# sensor.net
KiCad netlist of a schematic drawn in Altium Designer
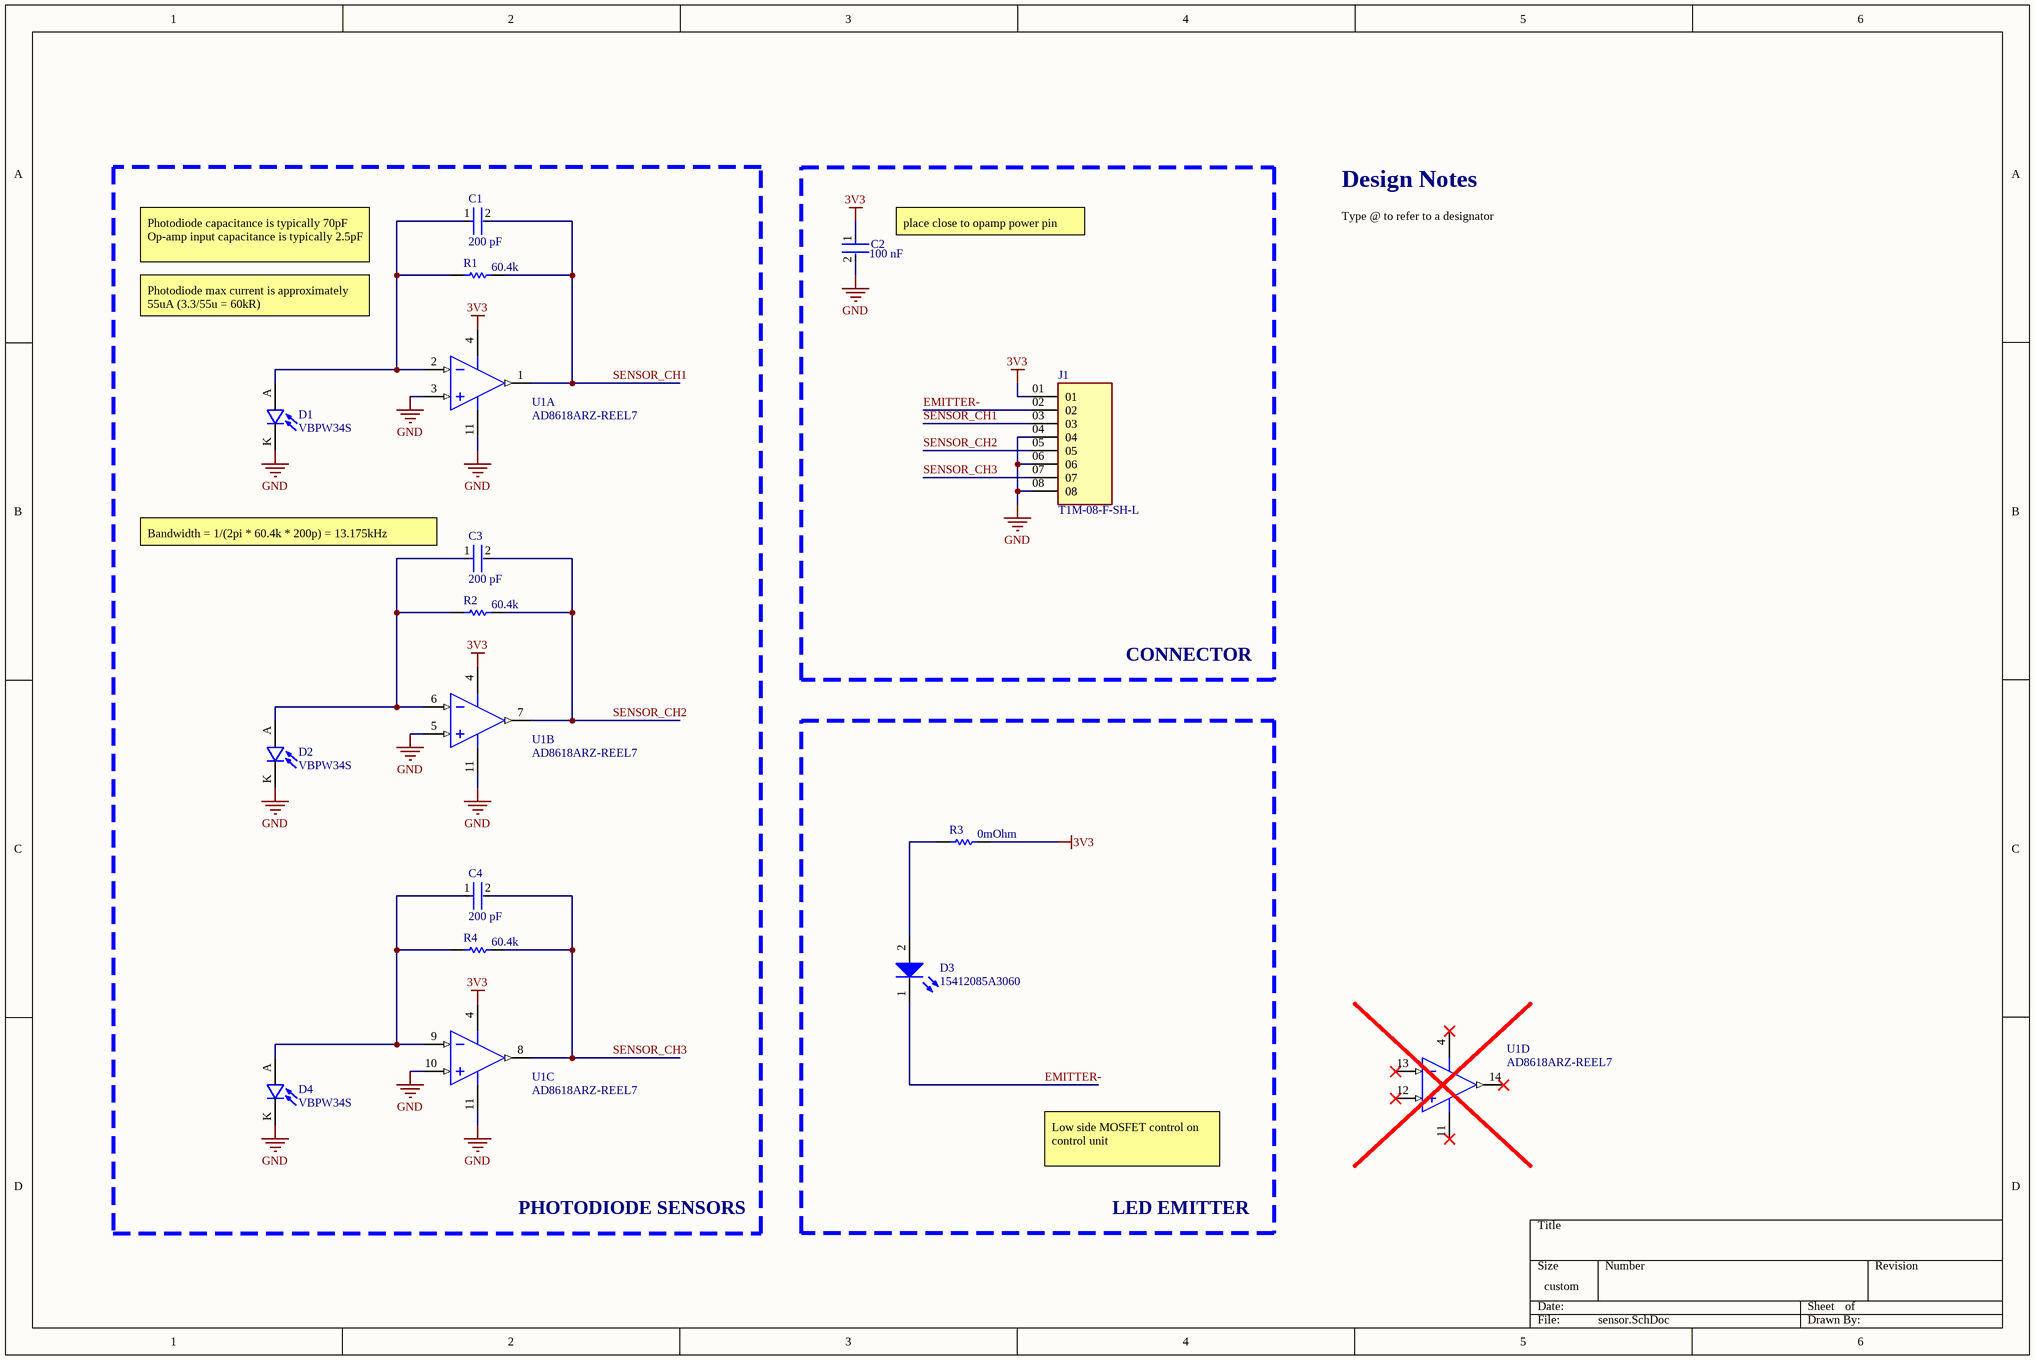
[diagram p0: sensor.SchDoc]

(export (version "E")
  (design (tool "Eeschema 10.0.6"))
  (components
    (comp (ref "C1")
      (value "C0603C201J5GACTU")
      (footprint "FP-C0603C-CF-MFG")
      (description "CAP CER 200PF 50V 5% NP0 0603")
      (fields
        (field (name "CAPACITANCE") "200 pF")
        (field (name "MANUFACTURER") "KEMET")
        (field (name "OCTOPART") "https://octopart.com/c0603c201j5gactu-kemet-9143917")
      )
      (libsource (lib "Altium Content Vault") (part "b4654b650e69147ec39a6b967a45e02"))
    )
    (comp (ref "C2")
      (value "CC0603KRX7R7BB104")
      (footprint "FP-CC0603-DA-MFG")
      (description "CAP CER 0.1UF 16V X7R 0603")
      (fields
        (field (name "OCTOPART") "https://octopart.com/cc0603krx7r7bb104-yageo-192941")
        (field (name "TOLERANCE") "0.1")
        (field (name "CAPACITANCE") "100 nF")
      )
      (libsource (lib "Altium Content Vault") (part "11868f565c42a9108669ba33697ecf6"))
    )
    (comp (ref "C3")
      (value "C0603C201J5GACTU")
      (footprint "FP-C0603C-CF-MFG")
      (description "CAP CER 200PF 50V 5% NP0 0603")
      (fields
        (field (name "CAPACITANCE") "200 pF")
        (field (name "MANUFACTURER") "KEMET")
        (field (name "OCTOPART") "https://octopart.com/c0603c201j5gactu-kemet-9143917")
      )
      (libsource (lib "Altium Content Vault") (part "b4654b650e69147ec39a6b967a45e02"))
    )
    (comp (ref "C4")
      (value "C0603C201J5GACTU")
      (footprint "FP-C0603C-CF-MFG")
      (description "CAP CER 200PF 50V 5% NP0 0603")
      (fields
        (field (name "CAPACITANCE") "200 pF")
        (field (name "MANUFACTURER") "KEMET")
        (field (name "OCTOPART") "https://octopart.com/c0603c201j5gactu-kemet-9143917")
      )
      (libsource (lib "Altium Content Vault") (part "b4654b650e69147ec39a6b967a45e02"))
    )
    (comp (ref "D1")
      (value "VBPW34S")
      (footprint "PcbLib1:XDCR_VBPW34S")
      (description "Photodiode 940nm 100ns 130Â° 2-SMD, Gull Wing")
      (fields (field (name "MF") "Vishay"))
      (libsource (lib "Schlib1") (part "VBPW34S"))
    )
    (comp (ref "D2")
      (value "VBPW34S")
      (footprint "PcbLib1:XDCR_VBPW34S")
      (description "Photodiode 940nm 100ns 130Â° 2-SMD, Gull Wing")
      (fields (field (name "MF") "Vishay"))
      (libsource (lib "Schlib1") (part "VBPW34S"))
    )
    (comp (ref "D3")
      (value "15412085A3060")
      (footprint "WL-SIRW_1206")
      (description "15412085A3060 WL-SIRW SMT Infrared Reverse mount Waterclear Dome")
      (libsource (lib "Altium Content Vault") (part "LED_Infrared_2A-1K"))
    )
    (comp (ref "D4")
      (value "VBPW34S")
      (footprint "PcbLib1:XDCR_VBPW34S")
      (description "Photodiode 940nm 100ns 130Â° 2-SMD, Gull Wing")
      (fields (field (name "MF") "Vishay"))
      (libsource (lib "Schlib1") (part "VBPW34S"))
    )
    (comp (ref "J1")
      (value "T1M-08-F-SH-L")
      (footprint "PcbLib1:SAMTEC_T1M-08-F-SH-L")
      (fields (field (name "MF") "Samtec Inc."))
      (libsource (lib "Schlib1") (part "T1M-08-F-SH-L"))
    )
    (comp (ref "R1")
      (value "RC0603FR-0760K4L")
      (footprint "RESC1608X55X25ML10T15")
      (fields (field (name "MANUFACTURER") "Yageo") (field (name "RESISTANCE") "60.4k"))
      (libsource (lib "Altium Content Vault") (part "RES"))
    )
    (comp (ref "R2")
      (value "RC0603FR-0760K4L")
      (footprint "RESC1608X55X25ML10T15")
      (fields (field (name "MANUFACTURER") "Yageo") (field (name "RESISTANCE") "60.4k"))
      (libsource (lib "Altium Content Vault") (part "RES"))
    )
    (comp (ref "R3")
      (value "RC0603JR-070RL")
      (footprint "RESC1608X55X25ML10T15")
      (description "Chip Resistor, 0 Ohm, +/- 5%, 0.1 W, -55 to 155 degC, 0603 (1608 Metric), RoHS, Tape and Reel")
      (fields
        (field (name "TOLERANCE") "5%")
        (field (name "RESISTANCE") "0mOhm")
        (field (name "MANUFACTURER") "Yageo")
      )
      (libsource (lib "Altium Content Vault") (part "RES-2"))
    )
    (comp (ref "R4")
      (value "RC0603FR-0760K4L")
      (footprint "RESC1608X55X25ML10T15")
      (fields (field (name "MANUFACTURER") "Yageo") (field (name "RESISTANCE") "60.4k"))
      (libsource (lib "Altium Content Vault") (part "RES"))
    )
    (comp (ref "U1")
      (value "AD8618ARZ-REEL7")
      (footprint "ADI-R-14_M")
      (fields (field (name "GENERIC PART NUMBER") "AD8618") (field (name "MANUFACTURER") "Analog Devices"))
      (libsource (lib "Altium Content Vault") (part "ADI-ADxxxx_OPxxxx-X-14"))
    )
  )
  (nets
    (net (code "1") (name "/EMITTER-") (class "Default")
      (node (ref "D3") (pin "1") (pinfunction "K_1") (pintype "passive"))
      (node (ref "J1") (pin "02") (pinfunction "02_02") (pintype "passive"))
    )
    (net (code "2") (name "/SENSOR_CH1") (class "Default")
      (node (ref "C1") (pin "2") (pinfunction "2_2") (pintype "passive"))
      (node (ref "J1") (pin "03") (pinfunction "03_03") (pintype "passive"))
      (node (ref "R1") (pin "2") (pinfunction "2_2") (pintype "passive"))
      (node (ref "U1") (pin "1") (pinfunction "OUT_A_1") (pintype "output"))
    )
    (net (code "3") (name "/SENSOR_CH2") (class "Default")
      (node (ref "C3") (pin "2") (pinfunction "2_2") (pintype "passive"))
      (node (ref "J1") (pin "05") (pinfunction "05_05") (pintype "passive"))
      (node (ref "R2") (pin "2") (pinfunction "2_2") (pintype "passive"))
      (node (ref "U1") (pin "7") (pinfunction "OUT_B_7") (pintype "output"))
    )
    (net (code "4") (name "/SENSOR_CH3") (class "Default")
      (node (ref "C4") (pin "2") (pinfunction "2_2") (pintype "passive"))
      (node (ref "J1") (pin "07") (pinfunction "07_07") (pintype "passive"))
      (node (ref "R4") (pin "2") (pinfunction "2_2") (pintype "passive"))
      (node (ref "U1") (pin "8") (pinfunction "OUT_C_8") (pintype "output"))
    )
    (net (code "5") (name "3V3") (class "Default")
      (node (ref "C2") (pin "1") (pinfunction "1_1") (pintype "passive"))
      (node (ref "J1") (pin "01") (pinfunction "01_01") (pintype "passive"))
      (node (ref "R3") (pin "2") (pinfunction "2_2") (pintype "passive"))
      (node (ref "U1") (pin "4") (pinfunction "+V_4") (pintype "power_in"))
    )
    (net (code "6") (name "GND") (class "Default")
      (node (ref "C2") (pin "2") (pinfunction "2_2") (pintype "passive"))
      (node (ref "D1") (pin "K") (pinfunction "C_K") (pintype "passive"))
      (node (ref "D2") (pin "K") (pinfunction "C_K") (pintype "passive"))
      (node (ref "D4") (pin "K") (pinfunction "C_K") (pintype "passive"))
      (node (ref "J1") (pin "04") (pinfunction "04_04") (pintype "passive"))
      (node (ref "J1") (pin "06") (pinfunction "06_06") (pintype "passive"))
      (node (ref "J1") (pin "08") (pinfunction "08_08") (pintype "passive"))
      (node (ref "U1") (pin "10") (pinfunction "+IN_C_10") (pintype "input"))
      (node (ref "U1") (pin "11") (pinfunction "-V_11") (pintype "power_in"))
      (node (ref "U1") (pin "3") (pinfunction "+IN_A_3") (pintype "input"))
      (node (ref "U1") (pin "5") (pinfunction "+IN_B_5") (pintype "input"))
    )
    (net (code "7") (name "Net-(D3-A)") (class "Default")
      (node (ref "D3") (pin "2") (pinfunction "A_2") (pintype "passive"))
      (node (ref "R3") (pin "1") (pinfunction "1_1") (pintype "passive"))
    )
    (net (code "8") (name "Net-(U1A--IN_A)") (class "Default")
      (node (ref "C1") (pin "1") (pinfunction "1_1") (pintype "passive"))
      (node (ref "D1") (pin "A") (pinfunction "A_A") (pintype "passive"))
      (node (ref "R1") (pin "1") (pinfunction "1_1") (pintype "passive"))
      (node (ref "U1") (pin "2") (pinfunction "-IN_A_2") (pintype "input"))
    )
    (net (code "9") (name "Net-(U1B--IN_B)") (class "Default")
      (node (ref "C3") (pin "1") (pinfunction "1_1") (pintype "passive"))
      (node (ref "D2") (pin "A") (pinfunction "A_A") (pintype "passive"))
      (node (ref "R2") (pin "1") (pinfunction "1_1") (pintype "passive"))
      (node (ref "U1") (pin "6") (pinfunction "-IN_B_6") (pintype "input"))
    )
    (net (code "10") (name "Net-(U1C--IN_C)") (class "Default")
      (node (ref "C4") (pin "1") (pinfunction "1_1") (pintype "passive"))
      (node (ref "D4") (pin "A") (pinfunction "A_A") (pintype "passive"))
      (node (ref "R4") (pin "1") (pinfunction "1_1") (pintype "passive"))
      (node (ref "U1") (pin "9") (pinfunction "-IN_C_9") (pintype "input"))
    )
    (net (code "11") (name "unconnected-(U1D-+IN_D-Pad12)") (class "Default")
      (node (ref "U1") (pin "12") (pinfunction "+IN_D_12") (pintype "input+no_connect"))
    )
    (net (code "12") (name "unconnected-(U1D-+V-Pad4)") (class "Default")
      (node (ref "U1") (pin "4") (pinfunction "+V_4") (pintype "power_in+no_connect"))
    )
    (net (code "13") (name "unconnected-(U1D--IN_D-Pad13)") (class "Default")
      (node (ref "U1") (pin "13") (pinfunction "-IN_D_13") (pintype "input+no_connect"))
    )
    (net (code "14") (name "unconnected-(U1D--V-Pad11)") (class "Default")
      (node (ref "U1") (pin "11") (pinfunction "-V_11") (pintype "power_in+no_connect"))
    )
    (net (code "15") (name "unconnected-(U1D-OUT_D-Pad14)") (class "Default")
      (node (ref "U1") (pin "14") (pinfunction "OUT_D_14") (pintype "output+no_connect"))
    )
  )
)
